# 05-LED-RED.net
KiCad netlist of a schematic drawn in Altium Designer
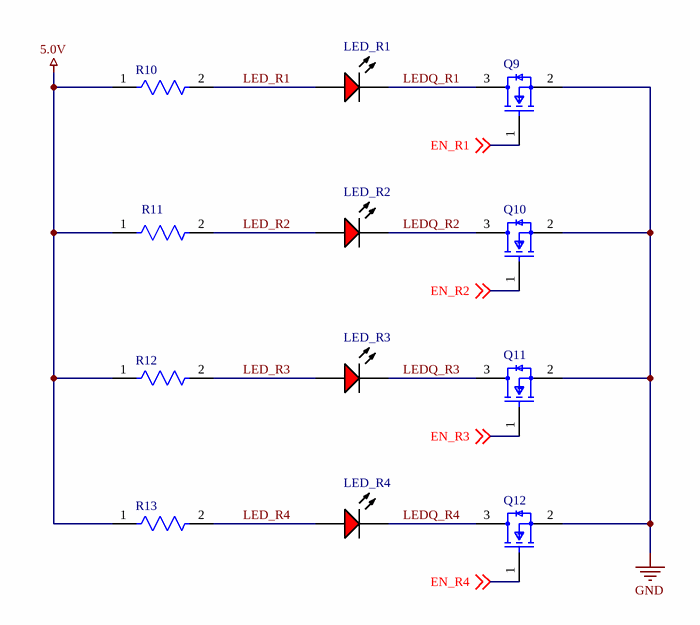
[diagram p0: 05-LED-RED.SchDoc]

(export (version "E")
  (design (tool "Eeschema 10.0.6"))
  (components
    (comp (ref "LED_R1")
      (value "SML-LX1206IC-TR")
      (footprint "LUMX-SML-LX1206IC_V")
      (description "LED Red, 65 mW, -40 to 85 degC, 2-Pin SMD, RoHS, Tape and Reel")
      (fields (field (name "MANUFACTURER") "Lumex"))
      (libsource (lib "Altium Content Vault") (part "LED-RED-AK-2"))
    )
    (comp (ref "LED_R2")
      (value "SML-LX1206IC-TR")
      (footprint "LUMX-SML-LX1206IC_V")
      (description "LED Red, 65 mW, -40 to 85 degC, 2-Pin SMD, RoHS, Tape and Reel")
      (fields (field (name "MANUFACTURER") "Lumex"))
      (libsource (lib "Altium Content Vault") (part "LED-RED-AK-2"))
    )
    (comp (ref "LED_R3")
      (value "SML-LX1206IC-TR")
      (footprint "LUMX-SML-LX1206IC_V")
      (description "LED Red, 65 mW, -40 to 85 degC, 2-Pin SMD, RoHS, Tape and Reel")
      (fields (field (name "MANUFACTURER") "Lumex"))
      (libsource (lib "Altium Content Vault") (part "LED-RED-AK-2"))
    )
    (comp (ref "LED_R4")
      (value "SML-LX1206IC-TR")
      (footprint "LUMX-SML-LX1206IC_V")
      (description "LED Red, 65 mW, -40 to 85 degC, 2-Pin SMD, RoHS, Tape and Reel")
      (fields (field (name "MANUFACTURER") "Lumex"))
      (libsource (lib "Altium Content Vault") (part "LED-RED-AK-2"))
    )
    (comp (ref "Q9")
      (value "2N7002-7-F")
      (footprint "FP-SOT23-MFG")
      (description "MOSFET N-CH 60V 115MA SOT23-3")
      (fields (field (name "VOLTAGE") "60V"))
      (libsource (lib "Altium Content Vault") (part "3b9c635fedb024a5347a57b145af9cc"))
    )
    (comp (ref "Q10")
      (value "2N7002-7-F")
      (footprint "FP-SOT23-MFG")
      (description "MOSFET N-CH 60V 115MA SOT23-3")
      (fields (field (name "VOLTAGE") "60V"))
      (libsource (lib "Altium Content Vault") (part "3b9c635fedb024a5347a57b145af9cc"))
    )
    (comp (ref "Q11")
      (value "2N7002-7-F")
      (footprint "FP-SOT23-MFG")
      (description "MOSFET N-CH 60V 115MA SOT23-3")
      (fields (field (name "VOLTAGE") "60V"))
      (libsource (lib "Altium Content Vault") (part "3b9c635fedb024a5347a57b145af9cc"))
    )
    (comp (ref "Q12")
      (value "2N7002-7-F")
      (footprint "FP-SOT23-MFG")
      (description "MOSFET N-CH 60V 115MA SOT23-3")
      (fields (field (name "VOLTAGE") "60V"))
      (libsource (lib "Altium Content Vault") (part "3b9c635fedb024a5347a57b145af9cc"))
    )
    (comp (ref "R10")
      (value "CRCW1206330RFKEA")
      (footprint "FP-CRCW1206-e3-IPC_A")
      (description "RES Thick Film, 330Ω, 1%, 0.25W, 100ppm/°C, 1206")
      (fields (field (name "TOLERANCE") "1%"))
      (libsource (lib "Altium Content Vault") (part "1029c3af85768c4190bb7ad29bc67b5"))
    )
    (comp (ref "R11")
      (value "CRCW1206330RFKEA")
      (footprint "FP-CRCW1206-e3-IPC_A")
      (description "RES Thick Film, 330Ω, 1%, 0.25W, 100ppm/°C, 1206")
      (fields (field (name "TOLERANCE") "1%"))
      (libsource (lib "Altium Content Vault") (part "1029c3af85768c4190bb7ad29bc67b5"))
    )
    (comp (ref "R12")
      (value "CRCW1206330RFKEA")
      (footprint "FP-CRCW1206-e3-IPC_A")
      (description "RES Thick Film, 330Ω, 1%, 0.25W, 100ppm/°C, 1206")
      (fields (field (name "TOLERANCE") "1%"))
      (libsource (lib "Altium Content Vault") (part "1029c3af85768c4190bb7ad29bc67b5"))
    )
    (comp (ref "R13")
      (value "CRCW1206330RFKEA")
      (footprint "FP-CRCW1206-e3-IPC_A")
      (description "RES Thick Film, 330Ω, 1%, 0.25W, 100ppm/°C, 1206")
      (fields (field (name "TOLERANCE") "1%"))
      (libsource (lib "Altium Content Vault") (part "1029c3af85768c4190bb7ad29bc67b5"))
    )
  )
  (nets
    (net (code "1") (name "/LEDQ_R1") (class "Default")
      (node (ref "LED_R1") (pin "2") (pinfunction "K_2") (pintype "passive"))
      (node (ref "Q9") (pin "3") (pinfunction "D_3") (pintype "passive"))
    )
    (net (code "2") (name "/LEDQ_R2") (class "Default")
      (node (ref "LED_R2") (pin "2") (pinfunction "K_2") (pintype "passive"))
      (node (ref "Q10") (pin "3") (pinfunction "D_3") (pintype "passive"))
    )
    (net (code "3") (name "/LEDQ_R3") (class "Default")
      (node (ref "LED_R3") (pin "2") (pinfunction "K_2") (pintype "passive"))
      (node (ref "Q11") (pin "3") (pinfunction "D_3") (pintype "passive"))
    )
    (net (code "4") (name "/LEDQ_R4") (class "Default")
      (node (ref "LED_R4") (pin "2") (pinfunction "K_2") (pintype "passive"))
      (node (ref "Q12") (pin "3") (pinfunction "D_3") (pintype "passive"))
    )
    (net (code "5") (name "/LED_R1") (class "Default")
      (node (ref "LED_R1") (pin "1") (pinfunction "A_1") (pintype "passive"))
      (node (ref "R10") (pin "2") (pinfunction "2_2") (pintype "passive"))
    )
    (net (code "6") (name "/LED_R2") (class "Default")
      (node (ref "LED_R2") (pin "1") (pinfunction "A_1") (pintype "passive"))
      (node (ref "R11") (pin "2") (pinfunction "2_2") (pintype "passive"))
    )
    (net (code "7") (name "/LED_R3") (class "Default")
      (node (ref "LED_R3") (pin "1") (pinfunction "A_1") (pintype "passive"))
      (node (ref "R12") (pin "2") (pinfunction "2_2") (pintype "passive"))
    )
    (net (code "8") (name "/LED_R4") (class "Default")
      (node (ref "LED_R4") (pin "1") (pinfunction "A_1") (pintype "passive"))
      (node (ref "R13") (pin "2") (pinfunction "2_2") (pintype "passive"))
    )
    (net (code "9") (name "5.0V") (class "Default")
      (node (ref "R10") (pin "1") (pinfunction "1_1") (pintype "passive"))
      (node (ref "R11") (pin "1") (pinfunction "1_1") (pintype "passive"))
      (node (ref "R12") (pin "1") (pinfunction "1_1") (pintype "passive"))
      (node (ref "R13") (pin "1") (pinfunction "1_1") (pintype "passive"))
    )
    (net (code "10") (name "EN_R1") (class "Default")
      (node (ref "Q9") (pin "1") (pinfunction "G_1") (pintype "passive"))
    )
    (net (code "11") (name "EN_R2") (class "Default")
      (node (ref "Q10") (pin "1") (pinfunction "G_1") (pintype "passive"))
    )
    (net (code "12") (name "EN_R3") (class "Default")
      (node (ref "Q11") (pin "1") (pinfunction "G_1") (pintype "passive"))
    )
    (net (code "13") (name "EN_R4") (class "Default")
      (node (ref "Q12") (pin "1") (pinfunction "G_1") (pintype "passive"))
    )
    (net (code "14") (name "GND") (class "Default")
      (node (ref "Q10") (pin "2") (pinfunction "S_2") (pintype "passive"))
      (node (ref "Q11") (pin "2") (pinfunction "S_2") (pintype "passive"))
      (node (ref "Q12") (pin "2") (pinfunction "S_2") (pintype "passive"))
      (node (ref "Q9") (pin "2") (pinfunction "S_2") (pintype "passive"))
    )
  )
)
